# EL-100-020-005-indicator-light.net
KiCad netlist of a schematic drawn in EAGLE
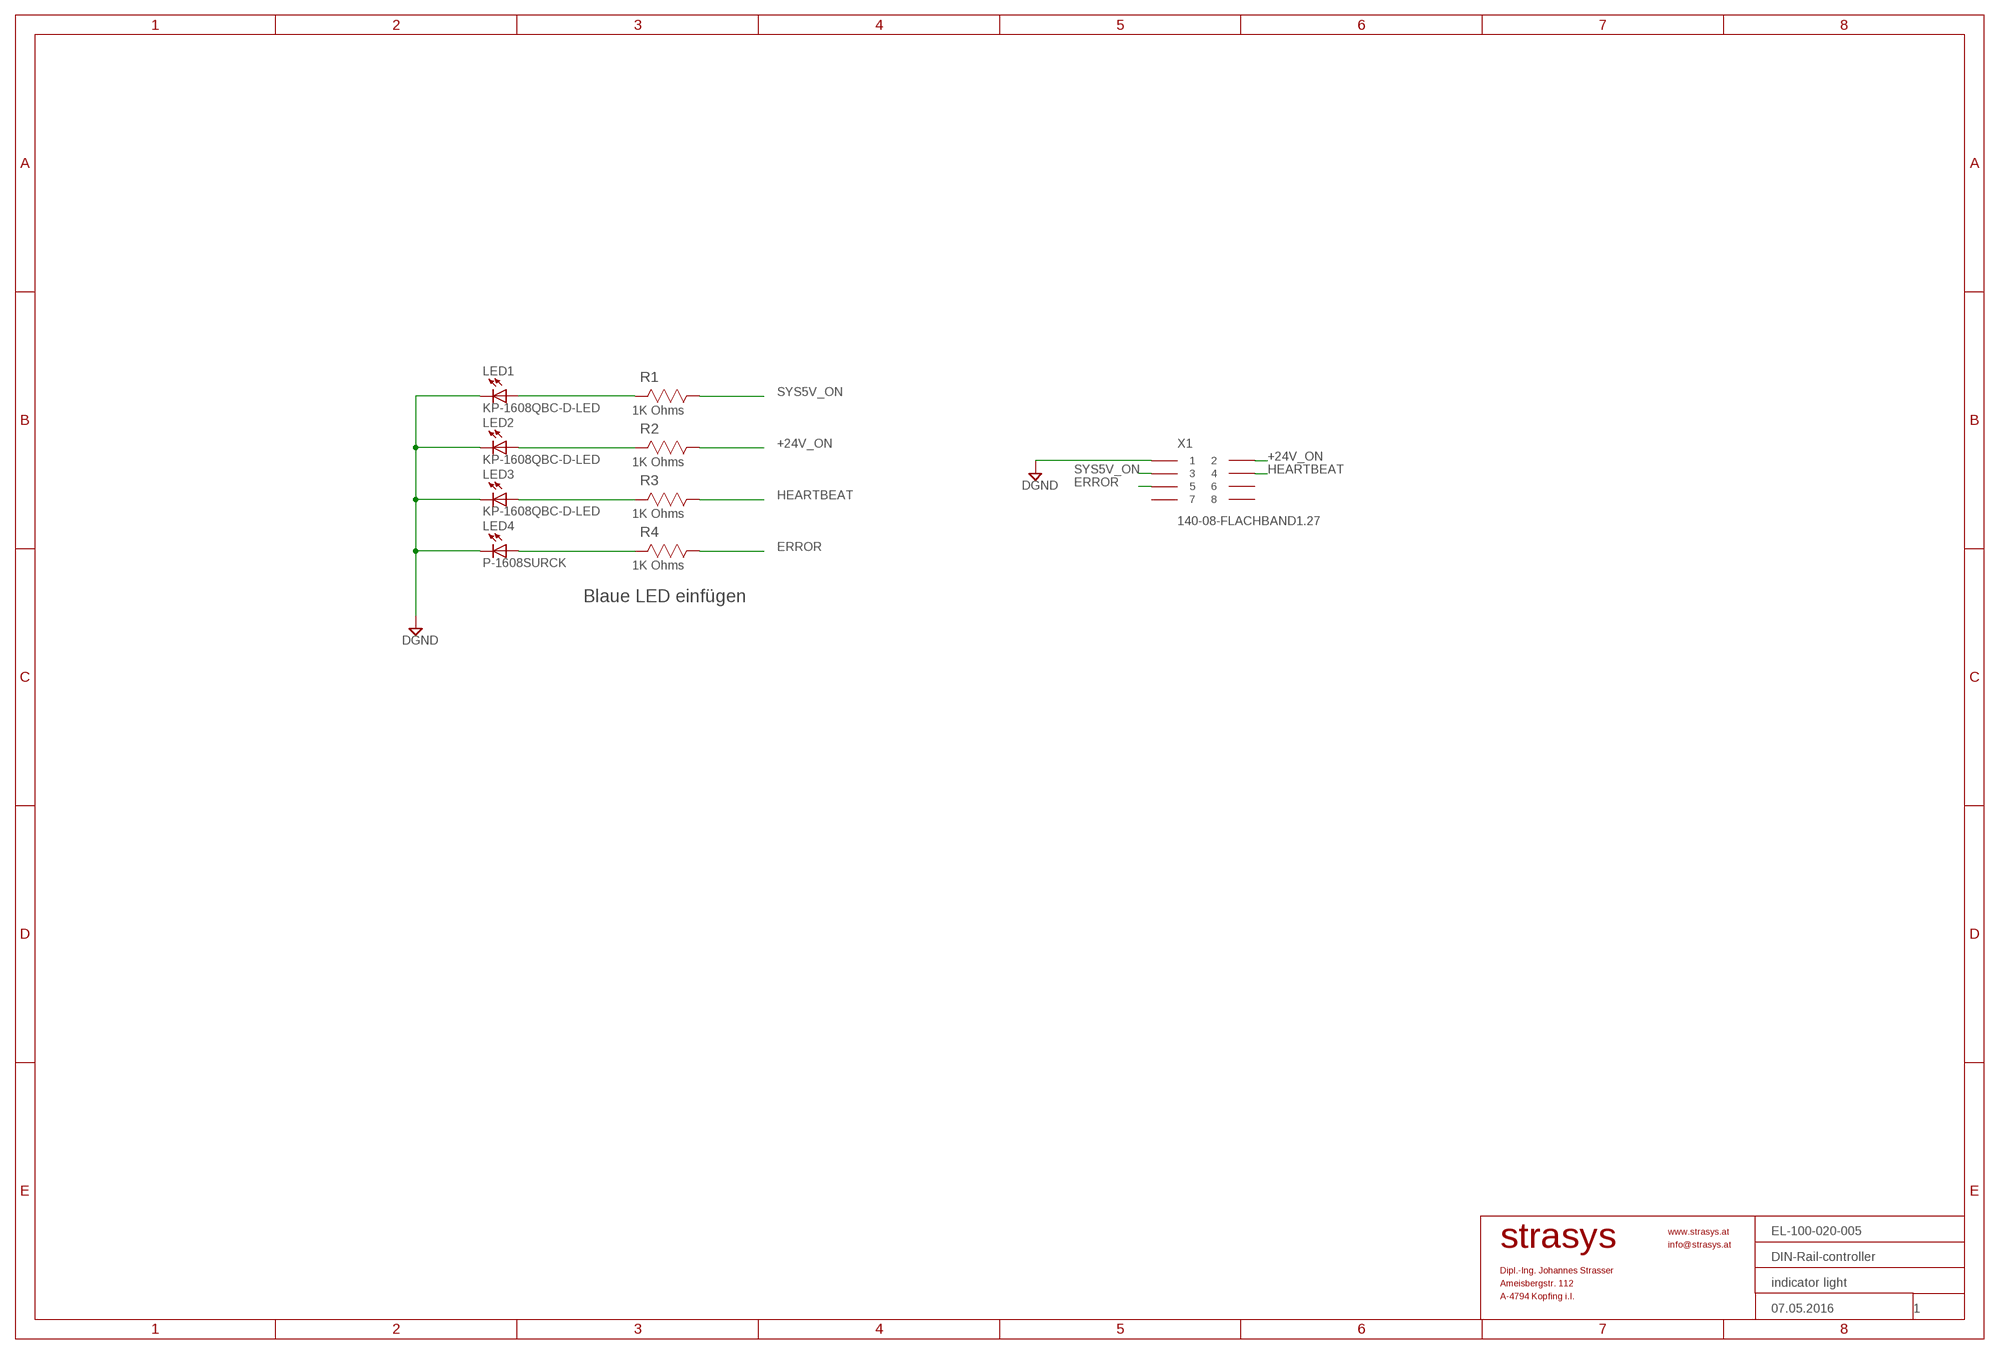
[diagram p0: schematic, sheet 1]

(export (version "E")
  (design (tool "Eeschema 10.0.6"))
  (components
    (comp (ref "LED1")
      (value "KP-1608QBC-D-LED")
      (footprint "eagle-import:KP-1608QBCD-D-LED")
      (libsource (lib "eagle-import") (part "KP-1608QBC-D-LED"))
    )
    (comp (ref "LED2")
      (value "KP-1608QBC-D-LED")
      (footprint "eagle-import:KP-1608QBCD-D-LED")
      (libsource (lib "eagle-import") (part "KP-1608QBC-D-LED"))
    )
    (comp (ref "LED3")
      (value "KP-1608QBC-D-LED")
      (footprint "eagle-import:KP-1608QBCD-D-LED")
      (libsource (lib "eagle-import") (part "KP-1608QBC-D-LED"))
    )
    (comp (ref "LED4")
      (value "P-1608SURCK")
      (footprint "eagle-import:KP-1608QBCD-D-LED")
      (fields (field (name "MPC") "KP-1608SURCK") (field (name "OC_FARNELL") "2290329"))
      (libsource (lib "eagle-import") (part "KP-1608QBC-D-LED"))
    )
    (comp (ref "R1")
      (value "1K Ohms")
      (footprint "eagle-import:RESC2013X65N")
      (fields (field (name "MPN") "CRCW08051K00JNEA") (field (name "TOLERANCE") "±5%"))
      (libsource (lib "eagle-import") (part "CRCW08051K00JNEA"))
    )
    (comp (ref "R2")
      (value "1K Ohms")
      (footprint "eagle-import:RESC2013X65N")
      (fields (field (name "MPN") "CRCW08051K00JNEA") (field (name "TOLERANCE") "±5%"))
      (libsource (lib "eagle-import") (part "CRCW08051K00JNEA"))
    )
    (comp (ref "R3")
      (value "1K Ohms")
      (footprint "eagle-import:RESC2013X65N")
      (fields (field (name "MPN") "CRCW08051K00JNEA") (field (name "TOLERANCE") "±5%"))
      (libsource (lib "eagle-import") (part "CRCW08051K00JNEA"))
    )
    (comp (ref "R4")
      (value "1K Ohms")
      (footprint "eagle-import:RESC2013X65N")
      (fields (field (name "MPN") "CRCW08051K00JNEA") (field (name "TOLERANCE") "±5%"))
      (libsource (lib "eagle-import") (part "CRCW08051K00JNEA"))
    )
    (comp (ref "X1")
      (value "140-08-FLACHBAND1.27")
      (footprint "eagle-import:2,54_2X8")
      (libsource (lib "eagle-import") (part "140-08-FLACHBAND1.27"))
    )
  )
  (nets
    (net (code "1") (name "/+24V_ON") (class "Default")
      (node (ref "R2") (pin "1") (pinfunction "1_1") (pintype "passive"))
      (node (ref "X1") (pin "P2") (pinfunction "2_P2") (pintype "bidirectional"))
    )
    (net (code "2") (name "/ERROR") (class "Default")
      (node (ref "R4") (pin "1") (pinfunction "1_1") (pintype "passive"))
      (node (ref "X1") (pin "P5") (pinfunction "5_P5") (pintype "bidirectional"))
    )
    (net (code "3") (name "/HEARTBEAT") (class "Default")
      (node (ref "R3") (pin "1") (pinfunction "1_1") (pintype "passive"))
      (node (ref "X1") (pin "P4") (pinfunction "4_P4") (pintype "bidirectional"))
    )
    (net (code "4") (name "/SYS5V_ON") (class "Default")
      (node (ref "R1") (pin "1") (pinfunction "1_1") (pintype "passive"))
      (node (ref "X1") (pin "P3") (pinfunction "3_P3") (pintype "bidirectional"))
    )
    (net (code "5") (name "DGND") (class "Default")
      (node (ref "LED1") (pin "2") (pinfunction "2_2") (pintype "passive"))
      (node (ref "LED2") (pin "2") (pinfunction "2_2") (pintype "passive"))
      (node (ref "LED3") (pin "2") (pinfunction "2_2") (pintype "passive"))
      (node (ref "LED4") (pin "2") (pinfunction "2_2") (pintype "passive"))
      (node (ref "X1") (pin "P1") (pinfunction "1_P1") (pintype "bidirectional"))
    )
    (net (code "6") (name "Net-(LED1-Pad1)") (class "Default")
      (node (ref "LED1") (pin "1") (pinfunction "1_1") (pintype "passive"))
      (node (ref "R1") (pin "2") (pinfunction "2_2") (pintype "passive"))
    )
    (net (code "7") (name "Net-(LED2-Pad1)") (class "Default")
      (node (ref "LED2") (pin "1") (pinfunction "1_1") (pintype "passive"))
      (node (ref "R2") (pin "2") (pinfunction "2_2") (pintype "passive"))
    )
    (net (code "8") (name "Net-(LED3-Pad1)") (class "Default")
      (node (ref "LED3") (pin "1") (pinfunction "1_1") (pintype "passive"))
      (node (ref "R3") (pin "2") (pinfunction "2_2") (pintype "passive"))
    )
    (net (code "9") (name "Net-(LED4-Pad1)") (class "Default")
      (node (ref "LED4") (pin "1") (pinfunction "1_1") (pintype "passive"))
      (node (ref "R4") (pin "2") (pinfunction "2_2") (pintype "passive"))
    )
    (net (code "10") (name "unconnected-(X1-6-PadP6)") (class "Default")
      (node (ref "X1") (pin "P6") (pinfunction "6_P6") (pintype "bidirectional"))
    )
    (net (code "11") (name "unconnected-(X1-7-PadP7)") (class "Default")
      (node (ref "X1") (pin "P7") (pinfunction "7_P7") (pintype "bidirectional"))
    )
    (net (code "12") (name "unconnected-(X1-8-PadP8)") (class "Default")
      (node (ref "X1") (pin "P8") (pinfunction "8_P8") (pintype "bidirectional"))
    )
  )
)
